# KT710GB.net
KiCad netlist of a schematic drawn in EasyEDA Pro
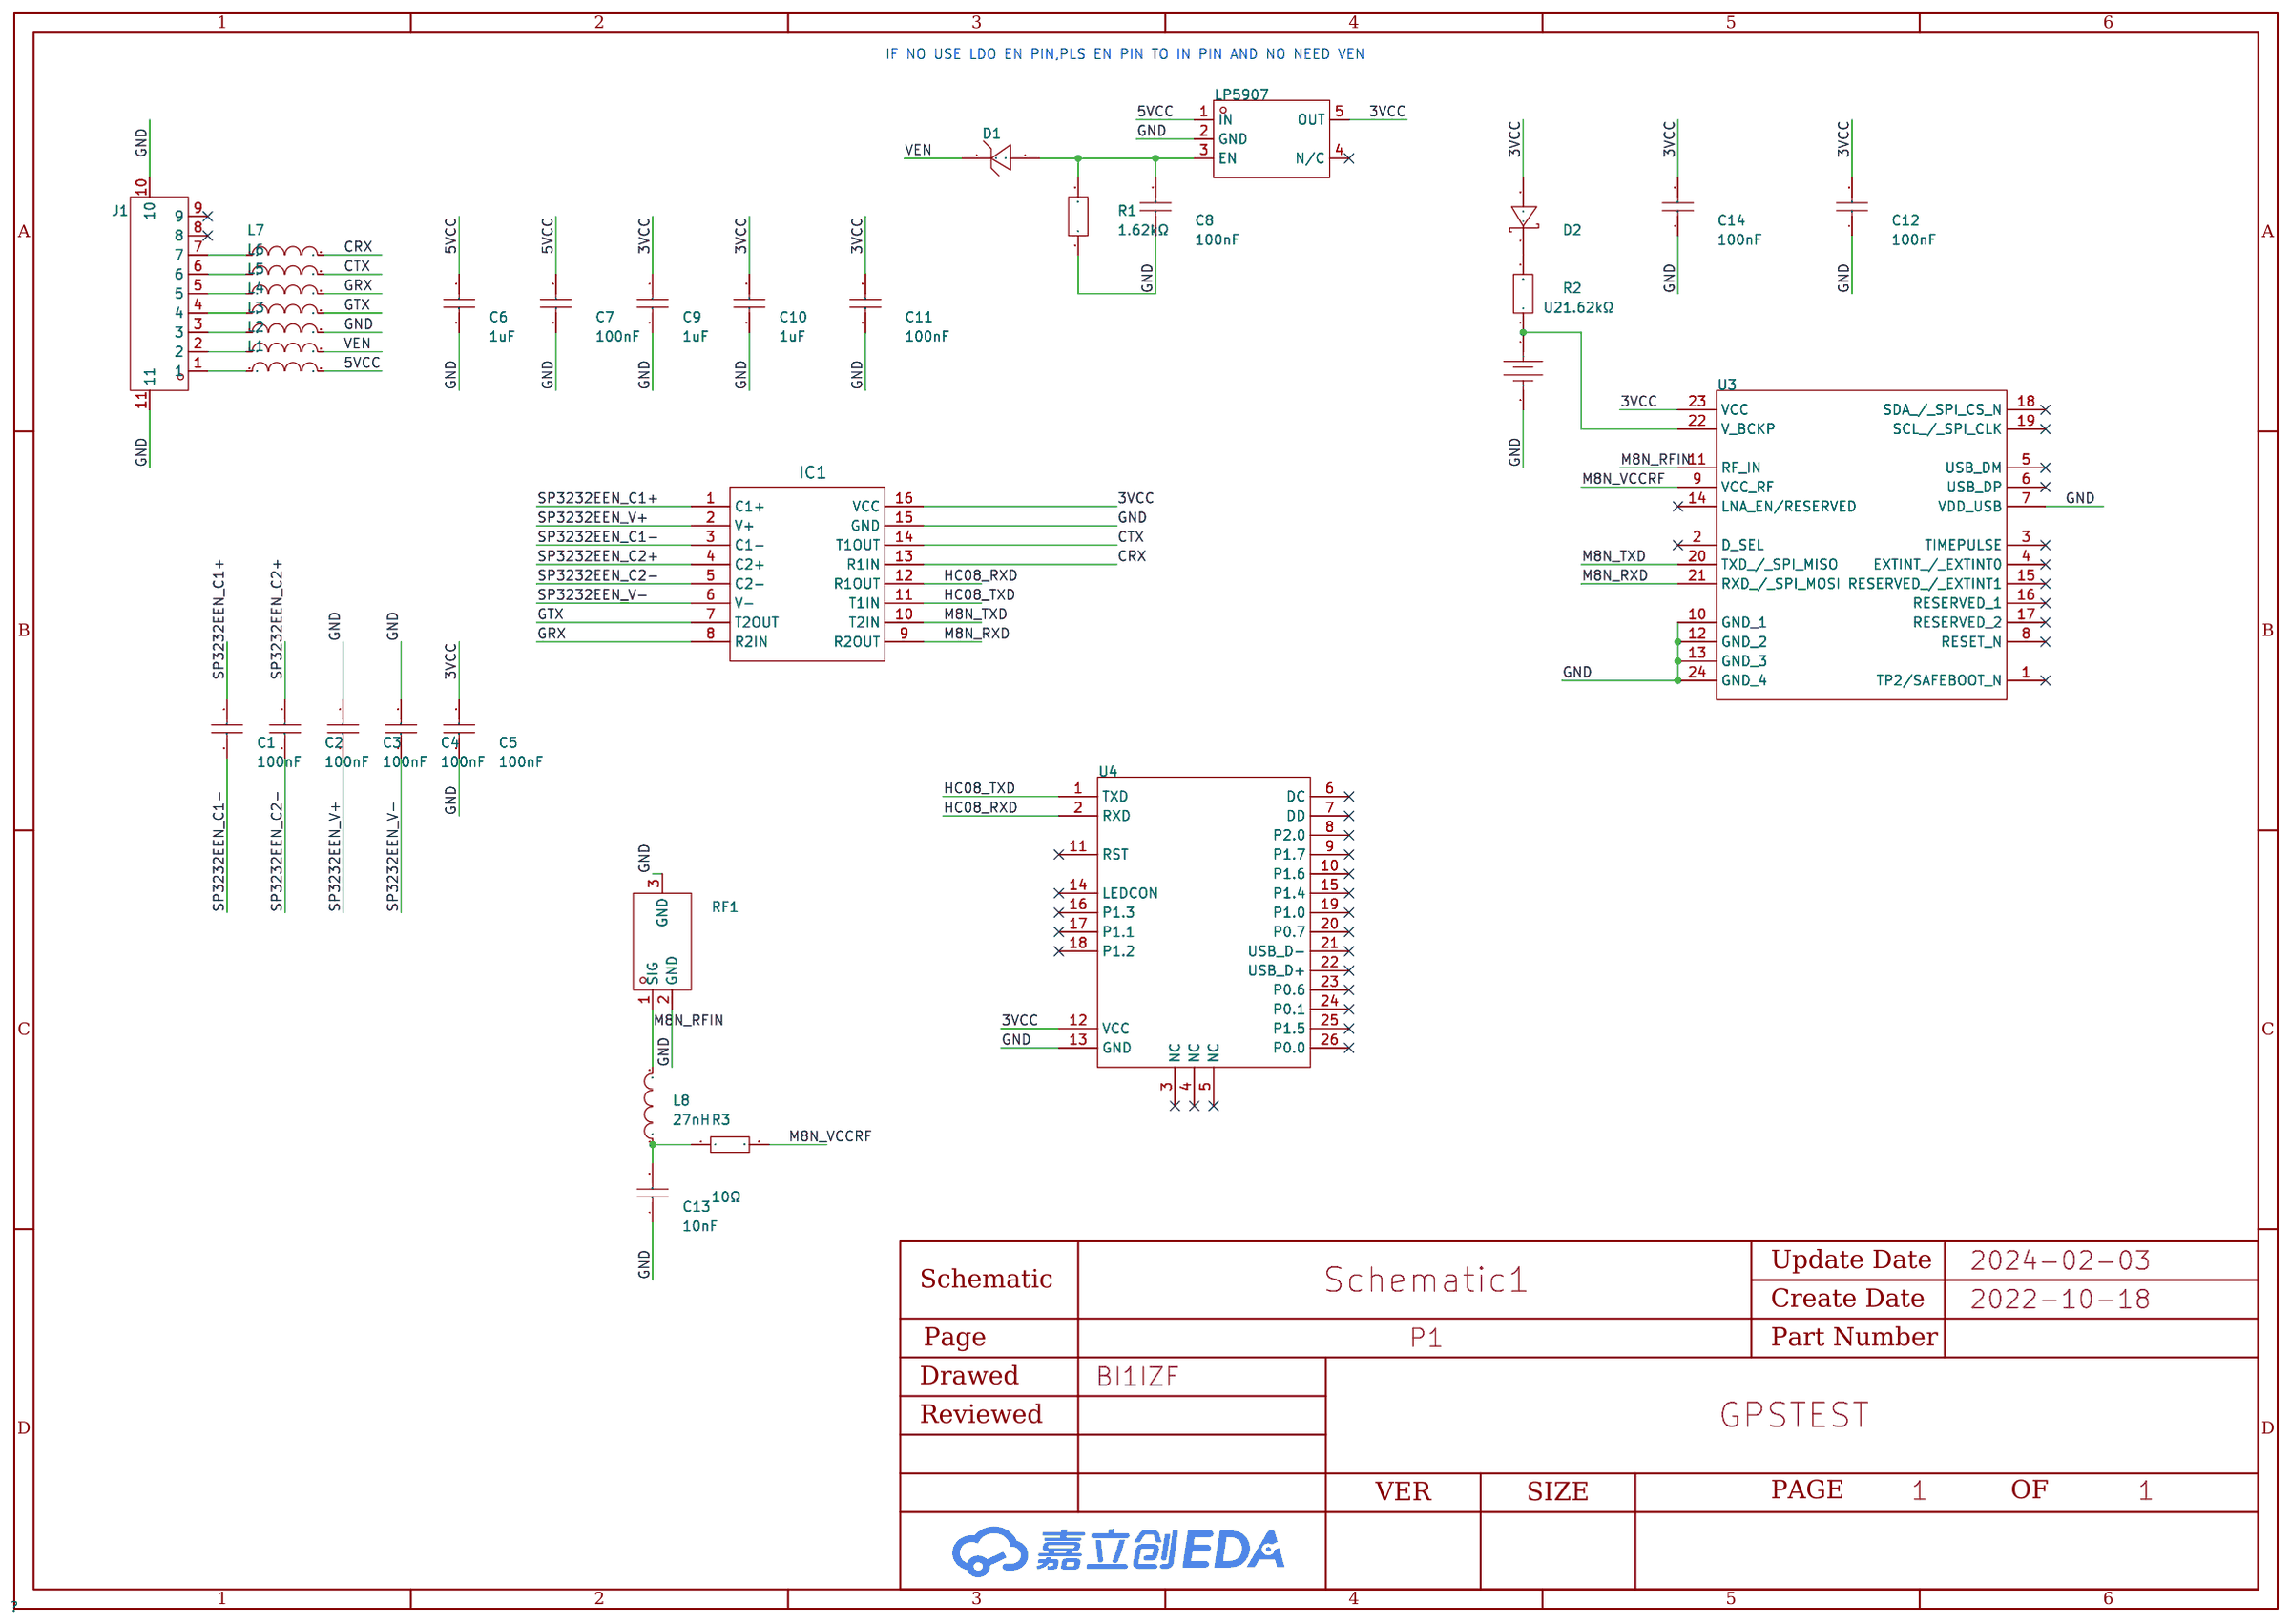
[diagram p0: schematic sheet]

(export (version "E")
  (design (tool "Eeschema 10.0.6"))
  (components
    (comp (ref "C1")
      (value "100nF")
      (footprint "easyedapro:C0603")
      (description "容值:100nF;精度:±10%;额定电压:50V;材质(温度系数):X7R;")
      (fields (field (name "Manufacturer Part") "0603B104K500NT") (field (name "Manufacturer") "FH(风华)"))
      (libsource (lib "easyedapro") (part "0603B104K500NT"))
    )
    (comp (ref "C2")
      (value "100nF")
      (footprint "easyedapro:C0603")
      (description "容值:100nF;精度:±10%;额定电压:50V;材质(温度系数):X7R;")
      (fields (field (name "Manufacturer Part") "0603B104K500NT") (field (name "Manufacturer") "FH(风华)"))
      (libsource (lib "easyedapro") (part "0603B104K500NT"))
    )
    (comp (ref "C3")
      (value "100nF")
      (footprint "easyedapro:C0603")
      (description "容值:100nF;精度:±10%;额定电压:50V;材质(温度系数):X7R;")
      (fields (field (name "Manufacturer Part") "0603B104K500NT") (field (name "Manufacturer") "FH(风华)"))
      (libsource (lib "easyedapro") (part "0603B104K500NT"))
    )
    (comp (ref "C4")
      (value "100nF")
      (footprint "easyedapro:C0603")
      (description "容值:100nF;精度:±10%;额定电压:50V;材质(温度系数):X7R;")
      (fields (field (name "Manufacturer Part") "0603B104K500NT") (field (name "Manufacturer") "FH(风华)"))
      (libsource (lib "easyedapro") (part "0603B104K500NT"))
    )
    (comp (ref "C5")
      (value "100nF")
      (footprint "easyedapro:C0603")
      (description "容值:100nF;精度:±10%;额定电压:50V;材质(温度系数):X7R;")
      (fields (field (name "Manufacturer Part") "0603B104K500NT") (field (name "Manufacturer") "FH(风华)"))
      (libsource (lib "easyedapro") (part "0603B104K500NT"))
    )
    (comp (ref "C6")
      (value "1uF")
      (footprint "easyedapro:C0603")
      (description "容值:1uF;精度:±10%;额定电压:25V;材质(温度系数):X7R;")
      (fields (field (name "Manufacturer Part") "0603B105K250NT") (field (name "Manufacturer") "FH(风华)"))
      (libsource (lib "easyedapro") (part "0603B105K250NT"))
    )
    (comp (ref "C7")
      (value "100nF")
      (footprint "easyedapro:C0603")
      (description "容值:100nF;精度:±10%;额定电压:50V;材质(温度系数):X7R;")
      (fields (field (name "Manufacturer Part") "0603B104K500NT") (field (name "Manufacturer") "FH(风华)"))
      (libsource (lib "easyedapro") (part "0603B104K500NT"))
    )
    (comp (ref "C8")
      (value "100nF")
      (footprint "easyedapro:C0603")
      (description "容值:100nF;精度:±10%;额定电压:50V;材质(温度系数):X7R;")
      (fields (field (name "Manufacturer Part") "0603B104K500NT") (field (name "Manufacturer") "FH(风华)"))
      (libsource (lib "easyedapro") (part "0603B104K500NT"))
    )
    (comp (ref "C9")
      (value "1uF")
      (footprint "easyedapro:C0603")
      (description "容值:1uF;精度:±10%;额定电压:25V;材质(温度系数):X7R;")
      (fields (field (name "Manufacturer Part") "0603B105K250NT") (field (name "Manufacturer") "FH(风华)"))
      (libsource (lib "easyedapro") (part "0603B105K250NT"))
    )
    (comp (ref "C10")
      (value "1uF")
      (footprint "easyedapro:C0603")
      (description "容值:1uF;精度:±10%;额定电压:25V;材质(温度系数):X7R;")
      (fields (field (name "Manufacturer Part") "0603B105K250NT") (field (name "Manufacturer") "FH(风华)"))
      (libsource (lib "easyedapro") (part "0603B105K250NT"))
    )
    (comp (ref "C11")
      (value "100nF")
      (footprint "easyedapro:C0603")
      (description "容值:100nF;精度:±10%;额定电压:50V;材质(温度系数):X7R;")
      (fields (field (name "Manufacturer Part") "0603B104K500NT") (field (name "Manufacturer") "FH(风华)"))
      (libsource (lib "easyedapro") (part "0603B104K500NT"))
    )
    (comp (ref "C12")
      (value "100nF")
      (footprint "easyedapro:C0603")
      (description "容值:100nF;精度:±10%;额定电压:50V;材质(温度系数):X7R;")
      (fields (field (name "Manufacturer Part") "0603B104K500NT") (field (name "Manufacturer") "FH(风华)"))
      (libsource (lib "easyedapro") (part "0603B104K500NT"))
    )
    (comp (ref "C13")
      (value "10nF")
      (footprint "easyedapro:C0603")
      (description "容值:10nF;精度:±10%;额定电压:50V;材质(温度系数):X7R;")
      (fields (field (name "Manufacturer Part") "0603B103K500NT") (field (name "Manufacturer") "FH(风华)"))
      (libsource (lib "easyedapro") (part "0603B103K500NT"))
    )
    (comp (ref "C14")
      (value "100nF")
      (footprint "easyedapro:C0603")
      (description "容值:100nF;精度:±10%;额定电压:50V;材质(温度系数):X7R;")
      (fields (field (name "Manufacturer Part") "0603B104K500NT") (field (name "Manufacturer") "FH(风华)"))
      (libsource (lib "easyedapro") (part "0603B104K500NT"))
    )
    (comp (ref "D1")
      (value "BZT52C2V0T-7")
      (footprint "easyedapro:SOD-523_L1.2-W0.8-LS1.6-RD")
      (description "二极管配置:独立式;稳压值(标称值):2V;稳压值(范围):1.91V~2.09V;功率:300mW;精度:±5%;")
      (fields (field (name "Manufacturer") "DIODES(美台)"))
      (libsource (lib "easyedapro") (part "BZT52C2V0T-7"))
    )
    (comp (ref "D2")
      (value "CUS10S30,H3F")
      (footprint "easyedapro:SOD-323_L1.8-W1.3-LS2.5-RD")
      (description "正向压降(Vf):230mV@100mA;直流反向耐压(Vr):30V;平均整流电流(Io):1A;")
      (fields (field (name "Manufacturer") "TOSHIBA(东芝)"))
      (libsource (lib "easyedapro") (part "CUS10S30,H3F"))
    )
    (comp (ref "IC1")
      (value "SP3232EEN-L/TR")
      (footprint "easyedapro:SOIC-16_L9.9-W3.9-P1.27-LS6.0-BL")
      (fields (field (name "Manufacturer") "EXAR"))
      (libsource (lib "easyedapro") (part "SP3232EEN-L/TR"))
    )
    (comp (ref "J1")
      (value "~")
      (footprint "easyedapro:PH2.0-9P")
      (libsource (lib "easyedapro") (part "PH2.0-9P_1"))
    )
    (comp (ref "L1")
      (value "BLM18AG601SN1D")
      (footprint "easyedapro:L0603")
      (description "标称阻抗@测试频率:600Ω@100MHz;误差:±25%;直流电阻(RDC):380mΩ;")
      (fields (field (name "Manufacturer") "muRata(村田)"))
      (libsource (lib "easyedapro") (part "BLM18AG601SN1D"))
    )
    (comp (ref "L2")
      (value "BLM18AG601SN1D")
      (footprint "easyedapro:L0603")
      (description "标称阻抗@测试频率:600Ω@100MHz;误差:±25%;直流电阻(RDC):380mΩ;")
      (fields (field (name "Manufacturer") "muRata(村田)"))
      (libsource (lib "easyedapro") (part "BLM18AG601SN1D"))
    )
    (comp (ref "L3")
      (value "BLM18AG601SN1D")
      (footprint "easyedapro:L0603")
      (description "标称阻抗@测试频率:600Ω@100MHz;误差:±25%;直流电阻(RDC):380mΩ;")
      (fields (field (name "Manufacturer") "muRata(村田)"))
      (libsource (lib "easyedapro") (part "BLM18AG601SN1D"))
    )
    (comp (ref "L4")
      (value "BLM18AG601SN1D")
      (footprint "easyedapro:L0603")
      (description "标称阻抗@测试频率:600Ω@100MHz;误差:±25%;直流电阻(RDC):380mΩ;")
      (fields (field (name "Manufacturer") "muRata(村田)"))
      (libsource (lib "easyedapro") (part "BLM18AG601SN1D"))
    )
    (comp (ref "L5")
      (value "BLM18AG601SN1D")
      (footprint "easyedapro:L0603")
      (description "标称阻抗@测试频率:600Ω@100MHz;误差:±25%;直流电阻(RDC):380mΩ;")
      (fields (field (name "Manufacturer") "muRata(村田)"))
      (libsource (lib "easyedapro") (part "BLM18AG601SN1D"))
    )
    (comp (ref "L6")
      (value "BLM18AG601SN1D")
      (footprint "easyedapro:L0603")
      (description "标称阻抗@测试频率:600Ω@100MHz;误差:±25%;直流电阻(RDC):380mΩ;")
      (fields (field (name "Manufacturer") "muRata(村田)"))
      (libsource (lib "easyedapro") (part "BLM18AG601SN1D"))
    )
    (comp (ref "L7")
      (value "BLM18AG601SN1D")
      (footprint "easyedapro:L0603")
      (description "标称阻抗@测试频率:600Ω@100MHz;误差:±25%;直流电阻(RDC):380mΩ;")
      (fields (field (name "Manufacturer") "muRata(村田)"))
      (libsource (lib "easyedapro") (part "BLM18AG601SN1D"))
    )
    (comp (ref "L8")
      (value "27nH")
      (footprint "easyedapro:L0603")
      (description "电感值:27nH;精度:±5%;额定电流:500mA;饱和电流(Isat):-;直流电阻(DCR):540mΩ;")
      (fields (field (name "Manufacturer Part") "LQG18HN27NJ00D") (field (name "Manufacturer") "muRata(村田)"))
      (libsource (lib "easyedapro") (part "LQG18HN27NJ00D"))
    )
    (comp (ref "LP5907")
      (value "LP5907MFX-3.3/NOPB")
      (footprint "easyedapro:SOT-23-5_L3.0-W1.7-P0.95-LS2.8-BR")
      (description "输出类型:固定;最大输入电压:5.5V;输出电压:3.3V;最大输出电流:250mA;电源纹波抑制比(PSRR):90dB;输出极性:正极;")
      (fields (field (name "Manufacturer") "TI(德州仪器)"))
      (libsource (lib "easyedapro") (part "LP5907MFX-3.3/NOPB"))
    )
    (comp (ref "R1")
      (value "1.62kΩ")
      (footprint "easyedapro:R0603")
      (description "电阻类型:厚膜电阻;阻值:1.62kΩ;精度:±1%;功率:100mW;温度系数:±100ppm/°C;")
      (fields (field (name "Manufacturer Part") "RK73H1JTTD1621F") (field (name "Manufacturer") "KOA"))
      (libsource (lib "easyedapro") (part "RK73H1JTTD1621F"))
    )
    (comp (ref "R2")
      (value "1.62kΩ")
      (footprint "easyedapro:R0603")
      (description "电阻类型:厚膜电阻;阻值:1.62kΩ;精度:±1%;功率:100mW;温度系数:±100ppm/°C;")
      (fields (field (name "Manufacturer Part") "RK73H1JTTD1621F") (field (name "Manufacturer") "KOA"))
      (libsource (lib "easyedapro") (part "RK73H1JTTD1621F"))
    )
    (comp (ref "R3")
      (value "10Ω")
      (footprint "easyedapro:R0402")
      (description "电阻类型:厚膜电阻;阻值:10Ω;精度:±1%;功率:100mW;最大工作电压:75V;温度系数:±100ppm/°C;")
      (fields (field (name "Manufacturer Part") "RK73H1ETTP10R0F") (field (name "Manufacturer") "KOA"))
      (libsource (lib "easyedapro") (part "RK73H1ETTP10R0F"))
    )
    (comp (ref "RF1")
      (value "BWIPX-1-001E")
      (footprint "easyedapro:IPEX-SMD_BWIPX-1-001E")
      (description "连接器类型:板端;接口类型:内针;端口数量:1;接口直径:-;接口长度/高度:-;频率-最大值:6GHz;射频系列:IPEX;阻抗:50Ω;样式:-;工作温度范围:-;")
      (fields (field (name "Manufacturer") "BAT WIRELESS(蝙蝠无线)"))
      (libsource (lib "easyedapro") (part "BWIPX-1-001E"))
    )
    (comp (ref "U2")
      (value "MS621FE-FL11E")
      (footprint "easyedapro:CAP-SMD_FL11E")
      (description "3.3V可充电纽扣电池 5.5mAH")
      (fields (field (name "Manufacturer") "Seiko(精工)"))
      (libsource (lib "easyedapro") (part "MS621FE-FL11E"))
    )
    (comp (ref "U3")
      (value "NEO-M8N")
      (footprint "easyedapro:BI1IZF_NEO-M8")
      (libsource (lib "easyedapro") (part "BI1IZF_NEO-M8N-0-10"))
    )
    (comp (ref "U4")
      (value "HC08")
      (description "HC08蓝牙芯片屏蔽版")
      (libsource (lib "easyedapro") (part "BI1IZF_HC08"))
    )
  )
  (nets
    (net (code "1") (name "/3VCC") (class "Default")
      (node (ref "C10") (pin "2") (pinfunction "2_2") (pintype "input"))
      (node (ref "C11") (pin "2") (pinfunction "2_2") (pintype "input"))
      (node (ref "C12") (pin "2") (pinfunction "2_2") (pintype "input"))
      (node (ref "C14") (pin "2") (pinfunction "2_2") (pintype "input"))
      (node (ref "C5") (pin "2") (pinfunction "2_2") (pintype "input"))
      (node (ref "C9") (pin "2") (pinfunction "2_2") (pintype "input"))
      (node (ref "D2") (pin "2") (pinfunction "A_2") (pintype "unspecified"))
      (node (ref "IC1") (pin "16") (pinfunction "VCC_16") (pintype "input"))
      (node (ref "LP5907") (pin "5") (pinfunction "OUT_5") (pintype "unspecified"))
      (node (ref "U3") (pin "23") (pinfunction "VCC_23") (pintype "input"))
      (node (ref "U4") (pin "12") (pinfunction "VCC_12") (pintype "input"))
    )
    (net (code "2") (name "/5VCC") (class "Default")
      (node (ref "C6") (pin "2") (pinfunction "2_2") (pintype "input"))
      (node (ref "C7") (pin "2") (pinfunction "2_2") (pintype "input"))
      (node (ref "L1") (pin "2") (pinfunction "2_2") (pintype "input"))
      (node (ref "LP5907") (pin "1") (pinfunction "IN_1") (pintype "unspecified"))
    )
    (net (code "3") (name "/CRX") (class "Default")
      (node (ref "IC1") (pin "13") (pinfunction "R1IN_13") (pintype "input"))
      (node (ref "L7") (pin "2") (pinfunction "2_2") (pintype "input"))
    )
    (net (code "4") (name "/CTX") (class "Default")
      (node (ref "IC1") (pin "14") (pinfunction "T1OUT_14") (pintype "input"))
      (node (ref "L6") (pin "2") (pinfunction "2_2") (pintype "input"))
    )
    (net (code "5") (name "/GND") (class "Default")
      (node (ref "C10") (pin "1") (pinfunction "1_1") (pintype "input"))
      (node (ref "C11") (pin "1") (pinfunction "1_1") (pintype "input"))
      (node (ref "C12") (pin "1") (pinfunction "1_1") (pintype "input"))
      (node (ref "C13") (pin "1") (pinfunction "1_1") (pintype "input"))
      (node (ref "C14") (pin "1") (pinfunction "1_1") (pintype "input"))
      (node (ref "C3") (pin "2") (pinfunction "2_2") (pintype "input"))
      (node (ref "C4") (pin "2") (pinfunction "2_2") (pintype "input"))
      (node (ref "C5") (pin "1") (pinfunction "1_1") (pintype "input"))
      (node (ref "C6") (pin "1") (pinfunction "1_1") (pintype "input"))
      (node (ref "C7") (pin "1") (pinfunction "1_1") (pintype "input"))
      (node (ref "C8") (pin "1") (pinfunction "1_1") (pintype "input"))
      (node (ref "C9") (pin "1") (pinfunction "1_1") (pintype "input"))
      (node (ref "IC1") (pin "15") (pinfunction "GND_15") (pintype "input"))
      (node (ref "J1") (pin "10") (pinfunction "10_10") (pintype "unspecified"))
      (node (ref "J1") (pin "11") (pinfunction "11_11") (pintype "unspecified"))
      (node (ref "L3") (pin "2") (pinfunction "2_2") (pintype "input"))
      (node (ref "LP5907") (pin "2") (pinfunction "GND_2") (pintype "unspecified"))
      (node (ref "R1") (pin "1") (pinfunction "1_1") (pintype "input"))
      (node (ref "RF1") (pin "2") (pinfunction "GND_2") (pintype "unspecified"))
      (node (ref "RF1") (pin "3") (pinfunction "GND_3") (pintype "unspecified"))
      (node (ref "U2") (pin "2") (pinfunction "-_2") (pintype "input"))
      (node (ref "U3") (pin "10") (pinfunction "GND_1_10") (pintype "input"))
      (node (ref "U3") (pin "12") (pinfunction "GND_2_12") (pintype "input"))
      (node (ref "U3") (pin "13") (pinfunction "GND_3_13") (pintype "input"))
      (node (ref "U3") (pin "24") (pinfunction "GND_4_24") (pintype "input"))
      (node (ref "U3") (pin "7") (pinfunction "VDD_USB_7") (pintype "input"))
      (node (ref "U4") (pin "13") (pinfunction "GND_13") (pintype "input"))
    )
    (net (code "6") (name "/GRX") (class "Default")
      (node (ref "IC1") (pin "8") (pinfunction "R2IN_8") (pintype "input"))
      (node (ref "L5") (pin "2") (pinfunction "2_2") (pintype "input"))
    )
    (net (code "7") (name "/GTX") (class "Default")
      (node (ref "IC1") (pin "7") (pinfunction "T2OUT_7") (pintype "input"))
      (node (ref "L4") (pin "2") (pinfunction "2_2") (pintype "input"))
    )
    (net (code "8") (name "/HC08_RXD") (class "Default")
      (node (ref "IC1") (pin "12") (pinfunction "R1OUT_12") (pintype "input"))
      (node (ref "U4") (pin "2") (pinfunction "RXD_2") (pintype "input"))
    )
    (net (code "9") (name "/HC08_TXD") (class "Default")
      (node (ref "IC1") (pin "11") (pinfunction "T1IN_11") (pintype "input"))
      (node (ref "U4") (pin "1") (pinfunction "TXD_1") (pintype "input"))
    )
    (net (code "10") (name "/M8N_RFIN") (class "Default")
      (node (ref "L8") (pin "2") (pinfunction "2_2") (pintype "unspecified"))
      (node (ref "RF1") (pin "1") (pinfunction "SIG_1") (pintype "unspecified"))
      (node (ref "U3") (pin "11") (pinfunction "RF_IN_11") (pintype "input"))
    )
    (net (code "11") (name "/M8N_RXD") (class "Default")
      (node (ref "IC1") (pin "9") (pinfunction "R2OUT_9") (pintype "input"))
      (node (ref "U3") (pin "21") (pinfunction "RXD_/_SPI_MOSI_21") (pintype "input"))
    )
    (net (code "12") (name "/M8N_TXD") (class "Default")
      (node (ref "IC1") (pin "10") (pinfunction "T2IN_10") (pintype "input"))
      (node (ref "U3") (pin "20") (pinfunction "TXD_/_SPI_MISO_20") (pintype "input"))
    )
    (net (code "13") (name "/M8N_VCCRF") (class "Default")
      (node (ref "R3") (pin "2") (pinfunction "2_2") (pintype "input"))
      (node (ref "U3") (pin "9") (pinfunction "VCC_RF_9") (pintype "input"))
    )
    (net (code "14") (name "/SP3232EEN_C1+") (class "Default")
      (node (ref "C1") (pin "2") (pinfunction "2_2") (pintype "input"))
      (node (ref "IC1") (pin "1") (pinfunction "C1+_1") (pintype "input"))
    )
    (net (code "15") (name "/SP3232EEN_C1-") (class "Default")
      (node (ref "C1") (pin "1") (pinfunction "1_1") (pintype "input"))
      (node (ref "IC1") (pin "3") (pinfunction "C1-_3") (pintype "input"))
    )
    (net (code "16") (name "/SP3232EEN_C2+") (class "Default")
      (node (ref "C2") (pin "2") (pinfunction "2_2") (pintype "input"))
      (node (ref "IC1") (pin "4") (pinfunction "C2+_4") (pintype "input"))
    )
    (net (code "17") (name "/SP3232EEN_C2-") (class "Default")
      (node (ref "C2") (pin "1") (pinfunction "1_1") (pintype "input"))
      (node (ref "IC1") (pin "5") (pinfunction "C2-_5") (pintype "input"))
    )
    (net (code "18") (name "/SP3232EEN_V+") (class "Default")
      (node (ref "C3") (pin "1") (pinfunction "1_1") (pintype "input"))
      (node (ref "IC1") (pin "2") (pinfunction "V+_2") (pintype "input"))
    )
    (net (code "19") (name "/SP3232EEN_V-") (class "Default")
      (node (ref "C4") (pin "1") (pinfunction "1_1") (pintype "input"))
      (node (ref "IC1") (pin "6") (pinfunction "V-_6") (pintype "input"))
    )
    (net (code "20") (name "/VEN") (class "Default")
      (node (ref "D1") (pin "1") (pinfunction "1_1") (pintype "input"))
      (node (ref "L2") (pin "2") (pinfunction "2_2") (pintype "input"))
    )
    (net (code "21") (name "Net-(C13-Pad2)") (class "Default")
      (node (ref "C13") (pin "2") (pinfunction "2_2") (pintype "input"))
      (node (ref "L8") (pin "1") (pinfunction "1_1") (pintype "unspecified"))
      (node (ref "R3") (pin "1") (pinfunction "1_1") (pintype "input"))
    )
    (net (code "22") (name "Net-(D2-K)") (class "Default")
      (node (ref "D2") (pin "1") (pinfunction "K_1") (pintype "unspecified"))
      (node (ref "R2") (pin "2") (pinfunction "2_2") (pintype "input"))
    )
    (net (code "23") (name "Net-(J1-Pad1)") (class "Default")
      (node (ref "J1") (pin "1") (pinfunction "1_1") (pintype "unspecified"))
      (node (ref "L1") (pin "1") (pinfunction "1_1") (pintype "input"))
    )
    (net (code "24") (name "Net-(J1-Pad2)") (class "Default")
      (node (ref "J1") (pin "2") (pinfunction "2_2") (pintype "unspecified"))
      (node (ref "L2") (pin "1") (pinfunction "1_1") (pintype "input"))
    )
    (net (code "25") (name "Net-(J1-Pad3)") (class "Default")
      (node (ref "J1") (pin "3") (pinfunction "3_3") (pintype "unspecified"))
      (node (ref "L3") (pin "1") (pinfunction "1_1") (pintype "input"))
    )
    (net (code "26") (name "Net-(J1-Pad4)") (class "Default")
      (node (ref "J1") (pin "4") (pinfunction "4_4") (pintype "unspecified"))
      (node (ref "L4") (pin "1") (pinfunction "1_1") (pintype "input"))
    )
    (net (code "27") (name "Net-(J1-Pad5)") (class "Default")
      (node (ref "J1") (pin "5") (pinfunction "5_5") (pintype "unspecified"))
      (node (ref "L5") (pin "1") (pinfunction "1_1") (pintype "input"))
    )
    (net (code "28") (name "Net-(J1-Pad6)") (class "Default")
      (node (ref "J1") (pin "6") (pinfunction "6_6") (pintype "unspecified"))
      (node (ref "L6") (pin "1") (pinfunction "1_1") (pintype "input"))
    )
    (net (code "29") (name "Net-(J1-Pad7)") (class "Default")
      (node (ref "J1") (pin "7") (pinfunction "7_7") (pintype "unspecified"))
      (node (ref "L7") (pin "1") (pinfunction "1_1") (pintype "input"))
    )
    (net (code "30") (name "Net-(LP5907-EN)") (class "Default")
      (node (ref "C8") (pin "2") (pinfunction "2_2") (pintype "input"))
      (node (ref "D1") (pin "2") (pinfunction "2_2") (pintype "input"))
      (node (ref "LP5907") (pin "3") (pinfunction "EN_3") (pintype "unspecified"))
      (node (ref "R1") (pin "2") (pinfunction "2_2") (pintype "input"))
    )
    (net (code "31") (name "Net-(U2-+)") (class "Default")
      (node (ref "R2") (pin "1") (pinfunction "1_1") (pintype "input"))
      (node (ref "U2") (pin "1") (pinfunction "+_1") (pintype "input"))
      (node (ref "U3") (pin "22") (pinfunction "V_BCKP_22") (pintype "input"))
    )
    (net (code "32") (name "unconnected-(J1-Pad8)") (class "Default")
      (node (ref "J1") (pin "8") (pinfunction "8_8") (pintype "unspecified+no_connect"))
    )
    (net (code "33") (name "unconnected-(J1-Pad9)") (class "Default")
      (node (ref "J1") (pin "9") (pinfunction "9_9") (pintype "unspecified+no_connect"))
    )
    (net (code "34") (name "unconnected-(LP5907-N{slash}C-Pad4)") (class "Default")
      (node (ref "LP5907") (pin "4") (pinfunction "N/C_4") (pintype "unspecified+no_connect"))
    )
    (net (code "35") (name "unconnected-(U3-D_SEL-Pad2)") (class "Default")
      (node (ref "U3") (pin "2") (pinfunction "D_SEL_2") (pintype "input+no_connect"))
    )
    (net (code "36") (name "unconnected-(U3-EXTINT_{slash}_EXTINT0-Pad4)") (class "Default")
      (node (ref "U3") (pin "4") (pinfunction "EXTINT_/_EXTINT0_4") (pintype "input+no_connect"))
    )
    (net (code "37") (name "unconnected-(U3-LNA_EN{slash}RESERVED-Pad14)") (class "Default")
      (node (ref "U3") (pin "14") (pinfunction "LNA_EN/RESERVED_14") (pintype "input+no_connect"))
    )
    (net (code "38") (name "unconnected-(U3-RESERVED_1-Pad16)") (class "Default")
      (node (ref "U3") (pin "16") (pinfunction "RESERVED_1_16") (pintype "input+no_connect"))
    )
    (net (code "39") (name "unconnected-(U3-RESERVED_2-Pad17)") (class "Default")
      (node (ref "U3") (pin "17") (pinfunction "RESERVED_2_17") (pintype "input+no_connect"))
    )
    (net (code "40") (name "unconnected-(U3-RESERVED_{slash}_EXTINT1-Pad15)") (class "Default")
      (node (ref "U3") (pin "15") (pinfunction "RESERVED_/_EXTINT1_15") (pintype "input+no_connect"))
    )
    (net (code "41") (name "unconnected-(U3-RESET_N-Pad8)") (class "Default")
      (node (ref "U3") (pin "8") (pinfunction "RESET_N_8") (pintype "input+no_connect"))
    )
    (net (code "42") (name "unconnected-(U3-SCL_{slash}_SPI_CLK-Pad19)") (class "Default")
      (node (ref "U3") (pin "19") (pinfunction "SCL_/_SPI_CLK_19") (pintype "input+no_connect"))
    )
    (net (code "43") (name "unconnected-(U3-SDA_{slash}_SPI_CS_N-Pad18)") (class "Default")
      (node (ref "U3") (pin "18") (pinfunction "SDA_/_SPI_CS_N_18") (pintype "input+no_connect"))
    )
    (net (code "44") (name "unconnected-(U3-TIMEPULSE-Pad3)") (class "Default")
      (node (ref "U3") (pin "3") (pinfunction "TIMEPULSE_3") (pintype "input+no_connect"))
    )
    (net (code "45") (name "unconnected-(U3-TP2{slash}SAFEBOOT_N-Pad1)") (class "Default")
      (node (ref "U3") (pin "1") (pinfunction "TP2/SAFEBOOT_N_1") (pintype "input+no_connect"))
    )
    (net (code "46") (name "unconnected-(U3-USB_DM-Pad5)") (class "Default")
      (node (ref "U3") (pin "5") (pinfunction "USB_DM_5") (pintype "input+no_connect"))
    )
    (net (code "47") (name "unconnected-(U3-USB_DP-Pad6)") (class "Default")
      (node (ref "U3") (pin "6") (pinfunction "USB_DP_6") (pintype "input+no_connect"))
    )
    (net (code "48") (name "unconnected-(U4-DC-Pad6)") (class "Default")
      (node (ref "U4") (pin "6") (pinfunction "DC_6") (pintype "input+no_connect"))
    )
    (net (code "49") (name "unconnected-(U4-DD-Pad7)") (class "Default")
      (node (ref "U4") (pin "7") (pinfunction "DD_7") (pintype "input+no_connect"))
    )
    (net (code "50") (name "unconnected-(U4-LEDCON-Pad14)") (class "Default")
      (node (ref "U4") (pin "14") (pinfunction "LEDCON_14") (pintype "input+no_connect"))
    )
    (net (code "51") (name "unconnected-(U4-NC-Pad3)") (class "Default")
      (node (ref "U4") (pin "3") (pinfunction "NC_3") (pintype "input+no_connect"))
    )
    (net (code "52") (name "unconnected-(U4-NC-Pad4)") (class "Default")
      (node (ref "U4") (pin "4") (pinfunction "NC_4") (pintype "input+no_connect"))
    )
    (net (code "53") (name "unconnected-(U4-NC-Pad5)") (class "Default")
      (node (ref "U4") (pin "5") (pinfunction "NC_5") (pintype "input+no_connect"))
    )
    (net (code "54") (name "unconnected-(U4-P0.0-Pad26)") (class "Default")
      (node (ref "U4") (pin "26") (pinfunction "P0.0_26") (pintype "input+no_connect"))
    )
    (net (code "55") (name "unconnected-(U4-P0.1-Pad24)") (class "Default")
      (node (ref "U4") (pin "24") (pinfunction "P0.1_24") (pintype "input+no_connect"))
    )
    (net (code "56") (name "unconnected-(U4-P0.6-Pad23)") (class "Default")
      (node (ref "U4") (pin "23") (pinfunction "P0.6_23") (pintype "input+no_connect"))
    )
    (net (code "57") (name "unconnected-(U4-P0.7-Pad20)") (class "Default")
      (node (ref "U4") (pin "20") (pinfunction "P0.7_20") (pintype "input+no_connect"))
    )
    (net (code "58") (name "unconnected-(U4-P1.0-Pad19)") (class "Default")
      (node (ref "U4") (pin "19") (pinfunction "P1.0_19") (pintype "input+no_connect"))
    )
    (net (code "59") (name "unconnected-(U4-P1.1-Pad17)") (class "Default")
      (node (ref "U4") (pin "17") (pinfunction "P1.1_17") (pintype "input+no_connect"))
    )
    (net (code "60") (name "unconnected-(U4-P1.2-Pad18)") (class "Default")
      (node (ref "U4") (pin "18") (pinfunction "P1.2_18") (pintype "input+no_connect"))
    )
    (net (code "61") (name "unconnected-(U4-P1.3-Pad16)") (class "Default")
      (node (ref "U4") (pin "16") (pinfunction "P1.3_16") (pintype "input+no_connect"))
    )
    (net (code "62") (name "unconnected-(U4-P1.4-Pad15)") (class "Default")
      (node (ref "U4") (pin "15") (pinfunction "P1.4_15") (pintype "input+no_connect"))
    )
    (net (code "63") (name "unconnected-(U4-P1.5-Pad25)") (class "Default")
      (node (ref "U4") (pin "25") (pinfunction "P1.5_25") (pintype "input+no_connect"))
    )
    (net (code "64") (name "unconnected-(U4-P1.6-Pad10)") (class "Default")
      (node (ref "U4") (pin "10") (pinfunction "P1.6_10") (pintype "input+no_connect"))
    )
    (net (code "65") (name "unconnected-(U4-P1.7-Pad9)") (class "Default")
      (node (ref "U4") (pin "9") (pinfunction "P1.7_9") (pintype "input+no_connect"))
    )
    (net (code "66") (name "unconnected-(U4-P2.0-Pad8)") (class "Default")
      (node (ref "U4") (pin "8") (pinfunction "P2.0_8") (pintype "input+no_connect"))
    )
    (net (code "67") (name "unconnected-(U4-RST-Pad11)") (class "Default")
      (node (ref "U4") (pin "11") (pinfunction "RST_11") (pintype "input+no_connect"))
    )
    (net (code "68") (name "unconnected-(U4-USB_D+-Pad22)") (class "Default")
      (node (ref "U4") (pin "22") (pinfunction "USB_D+_22") (pintype "input+no_connect"))
    )
    (net (code "69") (name "unconnected-(U4-USB_D--Pad21)") (class "Default")
      (node (ref "U4") (pin "21") (pinfunction "USB_D-_21") (pintype "input+no_connect"))
    )
  )
)
